# v7_h_no_callsign.net
KiCad netlist of a schematic drawn in EasyEDA Pro
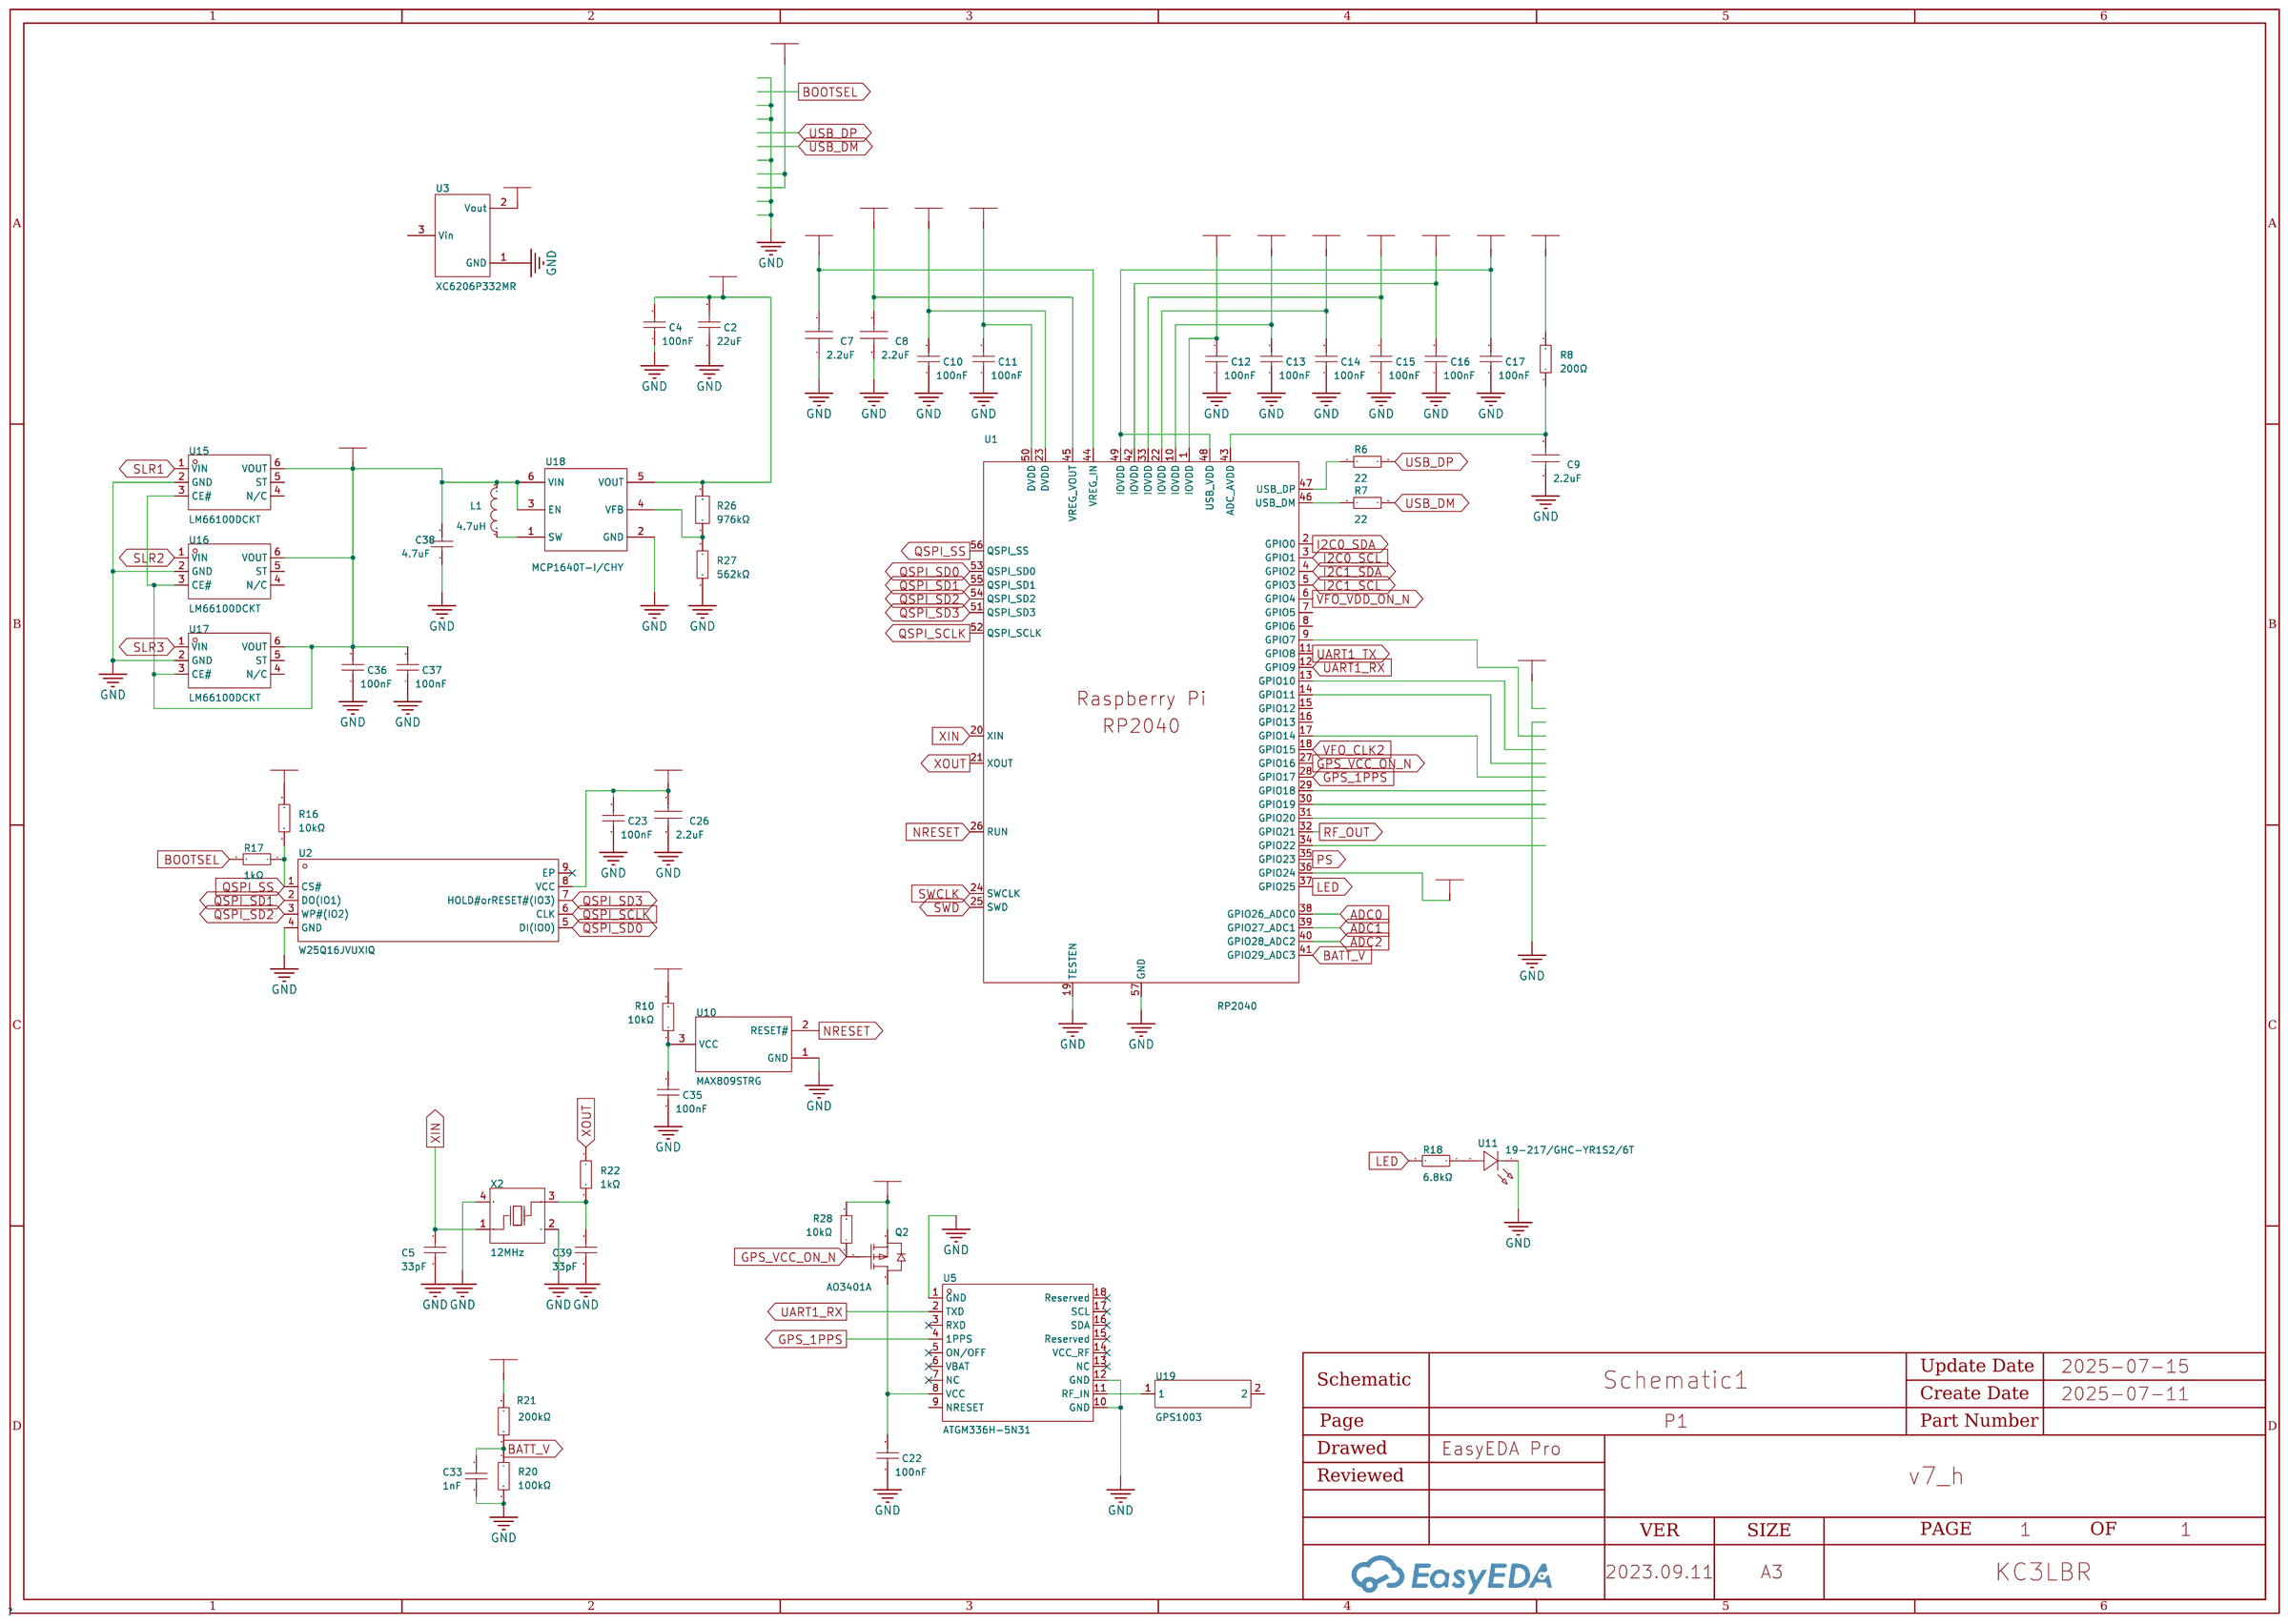
[diagram p0: schematic sheet]

(export (version "E")
  (design (tool "Eeschema 10.0.6"))
  (components
    (comp (ref "C2")
      (value "22uF")
      (footprint "easyedapro:C0603")
      (fields
        (field (name "Manufacturer Part") "CL10A226MQ8NRNC")
        (field (name "Manufacturer") "SAMSUNG(三星)")
      )
      (libsource (lib "easyedapro") (part "CL10A226MQ8NRNC"))
    )
    (comp (ref "C4")
      (value "100nF")
      (footprint "easyedapro:C0402_NEW")
      (fields
        (field (name "Manufacturer Part") "CL05B104KO5NNNC")
        (field (name "Manufacturer") "SAMSUNG(三星)")
      )
      (libsource (lib "easyedapro") (part "CL05B104KO5NNNC"))
    )
    (comp (ref "C5")
      (value "33pF")
      (footprint "easyedapro:C0402")
      (fields (field (name "Manufacturer Part") "0402CG330J500NT") (field (name "Manufacturer") "FH(风华)"))
      (libsource (lib "easyedapro") (part "0402CG330J500NT"))
    )
    (comp (ref "C7")
      (value "2.2uF")
      (footprint "easyedapro:C0402")
      (fields
        (field (name "Manufacturer Part") "CL05A225MQ5NSNC")
        (field (name "Manufacturer") "SAMSUNG(三星)")
      )
      (libsource (lib "easyedapro") (part "CL05A225MQ5NSNC"))
    )
    (comp (ref "C8")
      (value "2.2uF")
      (footprint "easyedapro:C0402")
      (fields
        (field (name "Manufacturer Part") "CL05A225MQ5NSNC")
        (field (name "Manufacturer") "SAMSUNG(三星)")
      )
      (libsource (lib "easyedapro") (part "CL05A225MQ5NSNC"))
    )
    (comp (ref "C9")
      (value "2.2uF")
      (footprint "easyedapro:C0402")
      (fields
        (field (name "Manufacturer Part") "CL05A225MQ5NSNC")
        (field (name "Manufacturer") "SAMSUNG(三星)")
      )
      (libsource (lib "easyedapro") (part "CL05A225MQ5NSNC"))
    )
    (comp (ref "C10")
      (value "100nF")
      (footprint "easyedapro:C0402_NEW")
      (fields
        (field (name "Manufacturer Part") "CL05B104KO5NNNC")
        (field (name "Manufacturer") "SAMSUNG(三星)")
      )
      (libsource (lib "easyedapro") (part "CL05B104KO5NNNC"))
    )
    (comp (ref "C11")
      (value "100nF")
      (footprint "easyedapro:C0402_NEW")
      (fields
        (field (name "Manufacturer Part") "CL05B104KO5NNNC")
        (field (name "Manufacturer") "SAMSUNG(三星)")
      )
      (libsource (lib "easyedapro") (part "CL05B104KO5NNNC"))
    )
    (comp (ref "C12")
      (value "100nF")
      (footprint "easyedapro:C0402_NEW")
      (fields
        (field (name "Manufacturer Part") "CL05B104KO5NNNC")
        (field (name "Manufacturer") "SAMSUNG(三星)")
      )
      (libsource (lib "easyedapro") (part "CL05B104KO5NNNC"))
    )
    (comp (ref "C13")
      (value "100nF")
      (footprint "easyedapro:C0402_NEW")
      (fields
        (field (name "Manufacturer Part") "CL05B104KO5NNNC")
        (field (name "Manufacturer") "SAMSUNG(三星)")
      )
      (libsource (lib "easyedapro") (part "CL05B104KO5NNNC"))
    )
    (comp (ref "C14")
      (value "100nF")
      (footprint "easyedapro:C0402_NEW")
      (fields
        (field (name "Manufacturer Part") "CL05B104KO5NNNC")
        (field (name "Manufacturer") "SAMSUNG(三星)")
      )
      (libsource (lib "easyedapro") (part "CL05B104KO5NNNC"))
    )
    (comp (ref "C15")
      (value "100nF")
      (footprint "easyedapro:C0402_NEW")
      (fields
        (field (name "Manufacturer Part") "CL05B104KO5NNNC")
        (field (name "Manufacturer") "SAMSUNG(三星)")
      )
      (libsource (lib "easyedapro") (part "CL05B104KO5NNNC"))
    )
    (comp (ref "C16")
      (value "100nF")
      (footprint "easyedapro:C0402_NEW")
      (fields
        (field (name "Manufacturer Part") "CL05B104KO5NNNC")
        (field (name "Manufacturer") "SAMSUNG(三星)")
      )
      (libsource (lib "easyedapro") (part "CL05B104KO5NNNC"))
    )
    (comp (ref "C17")
      (value "100nF")
      (footprint "easyedapro:C0402_NEW")
      (fields
        (field (name "Manufacturer Part") "CL05B104KO5NNNC")
        (field (name "Manufacturer") "SAMSUNG(三星)")
      )
      (libsource (lib "easyedapro") (part "CL05B104KO5NNNC"))
    )
    (comp (ref "C22")
      (value "100nF")
      (footprint "easyedapro:C0402_NEW")
      (fields
        (field (name "Manufacturer Part") "CL05B104KO5NNNC")
        (field (name "Manufacturer") "SAMSUNG(三星)")
      )
      (libsource (lib "easyedapro") (part "CL05B104KO5NNNC"))
    )
    (comp (ref "C23")
      (value "100nF")
      (footprint "easyedapro:C0402_NEW")
      (fields
        (field (name "Manufacturer Part") "CL05B104KO5NNNC")
        (field (name "Manufacturer") "SAMSUNG(三星)")
      )
      (libsource (lib "easyedapro") (part "CL05B104KO5NNNC"))
    )
    (comp (ref "C26")
      (value "2.2uF")
      (footprint "easyedapro:C0402")
      (fields
        (field (name "Manufacturer Part") "CL05A225MQ5NSNC")
        (field (name "Manufacturer") "SAMSUNG(三星)")
      )
      (libsource (lib "easyedapro") (part "CL05A225MQ5NSNC"))
    )
    (comp (ref "C33")
      (value "1nF")
      (footprint "easyedapro:C0402")
      (fields (field (name "Manufacturer Part") "0402B102K500NT") (field (name "Manufacturer") "FH(风华)"))
      (libsource (lib "easyedapro") (part "0402B102K500NT"))
    )
    (comp (ref "C35")
      (value "100nF")
      (footprint "easyedapro:C0402_NEW")
      (fields
        (field (name "Manufacturer Part") "CL05B104KO5NNNC")
        (field (name "Manufacturer") "SAMSUNG(三星)")
      )
      (libsource (lib "easyedapro") (part "CL05B104KO5NNNC"))
    )
    (comp (ref "C36")
      (value "100nF")
      (footprint "easyedapro:C0402_NEW")
      (fields
        (field (name "Manufacturer Part") "CL05B104KO5NNNC")
        (field (name "Manufacturer") "SAMSUNG(三星)")
      )
      (libsource (lib "easyedapro") (part "CL05B104KO5NNNC"))
    )
    (comp (ref "C37")
      (value "100nF")
      (footprint "easyedapro:C0402_NEW")
      (fields
        (field (name "Manufacturer Part") "CL05B104KO5NNNC")
        (field (name "Manufacturer") "SAMSUNG(三星)")
      )
      (libsource (lib "easyedapro") (part "CL05B104KO5NNNC"))
    )
    (comp (ref "C38")
      (value "4.7uF")
      (footprint "easyedapro:C0603")
      (fields
        (field (name "Manufacturer Part") "CL10A475KO8NNNC")
        (field (name "Manufacturer") "SAMSUNG(三星)")
      )
      (libsource (lib "easyedapro") (part "CL10A475KO8NNNC"))
    )
    (comp (ref "C39")
      (value "33pF")
      (footprint "easyedapro:C0402")
      (fields (field (name "Manufacturer Part") "0402CG330J500NT") (field (name "Manufacturer") "FH(风华)"))
      (libsource (lib "easyedapro") (part "0402CG330J500NT"))
    )
    (comp (ref "L1")
      (value "4.7uH")
      (footprint "easyedapro:IND-SMD_L2.5-W1.8")
      (fields
        (field (name "Manufacturer Part") "CBC2518T4R7M")
        (field (name "Manufacturer") "TAIYO YUDEN(太诱)")
      )
      (libsource (lib "easyedapro") (part "CBC2518T4R7M"))
    )
    (comp (ref "Q2")
      (value "AO3401A")
      (footprint "easyedapro:SOT-23_L2.9-W1.3-P1.90-LS2.4-BR")
      (fields (field (name "Manufacturer") "AOS"))
      (libsource (lib "easyedapro") (part "AO3401A"))
    )
    (comp (ref "R6")
      (value "22")
      (footprint "easyedapro:R0402")
      (fields
        (field (name "Manufacturer Part") "0402WGF220JTCE")
        (field (name "Manufacturer") "UNI-ROYAL(厚声)")
      )
      (libsource (lib "easyedapro") (part "0402WGF220JTCE"))
    )
    (comp (ref "R7")
      (value "22")
      (footprint "easyedapro:R0402")
      (fields
        (field (name "Manufacturer Part") "0402WGF220JTCE")
        (field (name "Manufacturer") "UNI-ROYAL(厚声)")
      )
      (libsource (lib "easyedapro") (part "0402WGF220JTCE"))
    )
    (comp (ref "R8")
      (value "200Ω")
      (footprint "easyedapro:R0402")
      (fields
        (field (name "Manufacturer Part") "0402WGF2000TCE")
        (field (name "Manufacturer") "UNI-ROYAL(厚声)")
      )
      (libsource (lib "easyedapro") (part "0402WGF2000TCE"))
    )
    (comp (ref "R10")
      (value "10kΩ")
      (footprint "easyedapro:R0402")
      (fields
        (field (name "Manufacturer Part") "0402WGF1002TCE")
        (field (name "Manufacturer") "UNI-ROYAL(厚声)")
      )
      (libsource (lib "easyedapro") (part "0402WGF1002TCE"))
    )
    (comp (ref "R16")
      (value "10kΩ")
      (footprint "easyedapro:R0402")
      (fields
        (field (name "Manufacturer Part") "0402WGF1002TCE")
        (field (name "Manufacturer") "UNI-ROYAL(厚声)")
      )
      (libsource (lib "easyedapro") (part "0402WGF1002TCE"))
    )
    (comp (ref "R17")
      (value "1kΩ")
      (footprint "easyedapro:R0402")
      (fields
        (field (name "Manufacturer Part") "0402WGF1001TCE")
        (field (name "Manufacturer") "UNI-ROYAL(厚声)")
      )
      (libsource (lib "easyedapro") (part "0402WGF1001TCE"))
    )
    (comp (ref "R18")
      (value "6.8kΩ")
      (footprint "easyedapro:R0402")
      (fields
        (field (name "Manufacturer Part") "0402WGF6801TCE")
        (field (name "Manufacturer") "UNI-ROYAL(厚声)")
      )
      (libsource (lib "easyedapro") (part "0402WGF6801TCE"))
    )
    (comp (ref "R20")
      (value "100kΩ")
      (footprint "easyedapro:R0402")
      (fields
        (field (name "Manufacturer Part") "0402WGF1003TCE")
        (field (name "Manufacturer") "UNI-ROYAL(厚声)")
      )
      (libsource (lib "easyedapro") (part "0402WGF1003TCE"))
    )
    (comp (ref "R21")
      (value "200kΩ")
      (footprint "easyedapro:R0402")
      (fields
        (field (name "Manufacturer Part") "0402WGF2003TCE")
        (field (name "Manufacturer") "UNI-ROYAL(厚声)")
      )
      (libsource (lib "easyedapro") (part "0402WGF2003TCE"))
    )
    (comp (ref "R22")
      (value "1kΩ")
      (footprint "easyedapro:R0402")
      (fields
        (field (name "Manufacturer Part") "0402WGF1001TCE")
        (field (name "Manufacturer") "UNI-ROYAL(厚声)")
      )
      (libsource (lib "easyedapro") (part "0402WGF1001TCE"))
    )
    (comp (ref "R26")
      (value "976kΩ")
      (footprint "easyedapro:R0402")
      (fields (field (name "Manufacturer Part") "RC0402FR-07976KL") (field (name "Manufacturer") "YAGEO(国巨)"))
      (libsource (lib "easyedapro") (part "RC0402FR-07976KL"))
    )
    (comp (ref "R27")
      (value "562kΩ")
      (footprint "easyedapro:R0402")
      (fields (field (name "Manufacturer Part") "RC0402FR-07562KL") (field (name "Manufacturer") "YAGEO(国巨)"))
      (libsource (lib "easyedapro") (part "RC0402FR-07562KL"))
    )
    (comp (ref "R28")
      (value "10kΩ")
      (footprint "easyedapro:R0402")
      (fields
        (field (name "Manufacturer Part") "0402WGF1002TCE")
        (field (name "Manufacturer") "UNI-ROYAL(厚声)")
      )
      (libsource (lib "easyedapro") (part "0402WGF1002TCE"))
    )
    (comp (ref "U1")
      (value "RP2040")
      (footprint "easyedapro:LQFN-56_L7.0-W7.0-P0.4-EP")
      (fields (field (name "Manufacturer") "Raspberry Pi(树莓派)"))
      (libsource (lib "easyedapro") (part "RP2040"))
    )
    (comp (ref "U2")
      (value "W25Q16JVUXIQ")
      (footprint "easyedapro:USON-8_L3.0-W2.0-P0.50-BL-EP")
      (fields (field (name "Manufacturer") "WINBOND(华邦)"))
      (libsource (lib "easyedapro") (part "W25Q16JVUXIQ"))
    )
    (comp (ref "U3")
      (value "XC6206P332MR")
      (footprint "easyedapro:SOT-23-3_L2.9-W1.6-P1.90-LS2.8-BR")
      (fields (field (name "Manufacturer") "GOODWORK(固得沃克)"))
      (libsource (lib "easyedapro") (part "XC6206P332MR"))
    )
    (comp (ref "U5")
      (value "ATGM336H-5N31")
      (footprint "easyedapro:GPSM-SMD_ATGM336H-TR")
      (fields (field (name "Manufacturer") "杭州中科微"))
      (libsource (lib "easyedapro") (part "ATGM336H-5N31"))
    )
    (comp (ref "U10")
      (value "MAX809STRG")
      (footprint "easyedapro:SOT-23-3_L2.9-W1.6-P1.90-LS2.8-BR")
      (fields (field (name "Manufacturer") "onsemi(安森美)"))
      (libsource (lib "easyedapro") (part "MAX809STRG"))
    )
    (comp (ref "U11")
      (value "19-217/GHC-YR1S2/6T")
      (footprint "easyedapro:LED0603-RD_GREEN")
      (fields (field (name "Manufacturer") "EVERLIGHT(亿光)"))
      (libsource (lib "easyedapro") (part "19-217/GHC-YR1S2/6T"))
    )
    (comp (ref "U15")
      (value "LM66100DCKT")
      (footprint "easyedapro:SC-70-6_L2.0-W1.3-P0.65-LS2.1-BL")
      (fields (field (name "Manufacturer") "TI(德州仪器)"))
      (libsource (lib "easyedapro") (part "LM66100DCKT"))
    )
    (comp (ref "U16")
      (value "LM66100DCKT")
      (footprint "easyedapro:SC-70-6_L2.0-W1.3-P0.65-LS2.1-BL")
      (fields (field (name "Manufacturer") "TI(德州仪器)"))
      (libsource (lib "easyedapro") (part "LM66100DCKT"))
    )
    (comp (ref "U17")
      (value "LM66100DCKT")
      (footprint "easyedapro:SC-70-6_L2.0-W1.3-P0.65-LS2.1-BL")
      (fields (field (name "Manufacturer") "TI(德州仪器)"))
      (libsource (lib "easyedapro") (part "LM66100DCKT"))
    )
    (comp (ref "U18")
      (value "MCP1640T-I/CHY")
      (footprint "easyedapro:SOT-23-6_L2.9-W1.6-P0.95-LS2.8-BR")
      (fields (field (name "Manufacturer") "MICROCHIP(美国微芯)"))
      (libsource (lib "easyedapro") (part "MCP1640T-I/CHY"))
    )
    (comp (ref "U19")
      (value "GPS1003")
      (footprint "easyedapro:ANT-SMD_L10.0-W3.0")
      (fields (field (name "Manufacturer") "Rainsun(霖昱微)"))
      (libsource (lib "easyedapro") (part "GPS1003"))
    )
    (comp (ref "X2")
      (value "12MHz")
      (footprint "easyedapro:OSC-SMD_4P-L3.2-W2.5-BL")
      (fields (field (name "Manufacturer Part") "X322512MSB4SI") (field (name "Manufacturer") "YXC(扬兴晶振)"))
      (libsource (lib "easyedapro") (part "X322512MSB4SI"))
    )
  )
  (nets
    (net (code "1") (name "1V1") (class "Default")
      (node (ref "C10") (pin "2") (pinfunction "2_2") (pintype "input"))
      (node (ref "C11") (pin "2") (pinfunction "2_2") (pintype "input"))
      (node (ref "C8") (pin "2") (pinfunction "2_2") (pintype "input"))
      (node (ref "U1") (pin "23") (pinfunction "DVDD_23") (pintype "bidirectional"))
      (node (ref "U1") (pin "45") (pinfunction "VREG_VOUT_45") (pintype "bidirectional"))
      (node (ref "U1") (pin "50") (pinfunction "DVDD_50") (pintype "bidirectional"))
    )
    (net (code "2") (name "3V3") (class "Default")
      (node (ref "C12") (pin "2") (pinfunction "2_2") (pintype "input"))
      (node (ref "C13") (pin "2") (pinfunction "2_2") (pintype "input"))
      (node (ref "C14") (pin "2") (pinfunction "2_2") (pintype "input"))
      (node (ref "C15") (pin "2") (pinfunction "2_2") (pintype "input"))
      (node (ref "C16") (pin "2") (pinfunction "2_2") (pintype "input"))
      (node (ref "C17") (pin "2") (pinfunction "2_2") (pintype "input"))
      (node (ref "C2") (pin "2") (pinfunction "2_2") (pintype "input"))
      (node (ref "C23") (pin "2") (pinfunction "2_2") (pintype "input"))
      (node (ref "C26") (pin "2") (pinfunction "2_2") (pintype "input"))
      (node (ref "C4") (pin "2") (pinfunction "2_2") (pintype "input"))
      (node (ref "C7") (pin "2") (pinfunction "2_2") (pintype "input"))
      (node (ref "Q2") (pin "2") (pinfunction "S_2") (pintype "input"))
      (node (ref "R10") (pin "2") (pinfunction "2_2") (pintype "input"))
      (node (ref "R16") (pin "2") (pinfunction "2_2") (pintype "input"))
      (node (ref "R26") (pin "2") (pinfunction "2_2") (pintype "unspecified"))
      (node (ref "R28") (pin "2") (pinfunction "2_2") (pintype "input"))
      (node (ref "R8") (pin "2") (pinfunction "2_2") (pintype "input"))
      (node (ref "U1") (pin "1") (pinfunction "IOVDD_1") (pintype "bidirectional"))
      (node (ref "U1") (pin "10") (pinfunction "IOVDD_10") (pintype "bidirectional"))
      (node (ref "U1") (pin "22") (pinfunction "IOVDD_22") (pintype "bidirectional"))
      (node (ref "U1") (pin "33") (pinfunction "IOVDD_33") (pintype "bidirectional"))
      (node (ref "U1") (pin "36") (pinfunction "GPIO24_36") (pintype "bidirectional"))
      (node (ref "U1") (pin "42") (pinfunction "IOVDD_42") (pintype "bidirectional"))
      (node (ref "U1") (pin "44") (pinfunction "VREG_IN_44") (pintype "bidirectional"))
      (node (ref "U1") (pin "48") (pinfunction "USB_VDD_48") (pintype "bidirectional"))
      (node (ref "U1") (pin "49") (pinfunction "IOVDD_49") (pintype "bidirectional"))
      (node (ref "U18") (pin "5") (pinfunction "VOUT_5") (pintype "input"))
      (node (ref "U2") (pin "8") (pinfunction "VCC_8") (pintype "input"))
      (node (ref "U3") (pin "2") (pinfunction "Vout_2") (pintype "input"))
    )
    (net (code "3") (name "ADC0") (class "Default")
      (node (ref "U1") (pin "38") (pinfunction "GPIO26_ADC0_38") (pintype "bidirectional"))
    )
    (net (code "4") (name "ADC1") (class "Default")
      (node (ref "U1") (pin "39") (pinfunction "GPIO27_ADC1_39") (pintype "bidirectional"))
    )
    (net (code "5") (name "ADC2") (class "Default")
      (node (ref "U1") (pin "40") (pinfunction "GPIO28_ADC2_40") (pintype "bidirectional"))
    )
    (net (code "6") (name "BATT_V") (class "Default")
      (node (ref "C33") (pin "2") (pinfunction "2_2") (pintype "input"))
      (node (ref "R20") (pin "1") (pinfunction "1_1") (pintype "input"))
      (node (ref "R21") (pin "1") (pinfunction "1_1") (pintype "input"))
      (node (ref "U1") (pin "41") (pinfunction "GPIO29_ADC3_41") (pintype "bidirectional"))
    )
    (net (code "7") (name "BOOTSEL") (class "Default")
      (node (ref "R17") (pin "2") (pinfunction "2_2") (pintype "input"))
    )
    (net (code "8") (name "GND") (class "Default")
      (node (ref "C10") (pin "1") (pinfunction "1_1") (pintype "input"))
      (node (ref "C11") (pin "1") (pinfunction "1_1") (pintype "input"))
      (node (ref "C12") (pin "1") (pinfunction "1_1") (pintype "input"))
      (node (ref "C13") (pin "1") (pinfunction "1_1") (pintype "input"))
      (node (ref "C14") (pin "1") (pinfunction "1_1") (pintype "input"))
      (node (ref "C15") (pin "1") (pinfunction "1_1") (pintype "input"))
      (node (ref "C16") (pin "1") (pinfunction "1_1") (pintype "input"))
      (node (ref "C17") (pin "1") (pinfunction "1_1") (pintype "input"))
      (node (ref "C2") (pin "1") (pinfunction "1_1") (pintype "input"))
      (node (ref "C22") (pin "1") (pinfunction "1_1") (pintype "input"))
      (node (ref "C23") (pin "1") (pinfunction "1_1") (pintype "input"))
      (node (ref "C26") (pin "1") (pinfunction "1_1") (pintype "input"))
      (node (ref "C33") (pin "1") (pinfunction "1_1") (pintype "input"))
      (node (ref "C35") (pin "1") (pinfunction "1_1") (pintype "input"))
      (node (ref "C36") (pin "1") (pinfunction "1_1") (pintype "input"))
      (node (ref "C37") (pin "1") (pinfunction "1_1") (pintype "input"))
      (node (ref "C38") (pin "1") (pinfunction "1_1") (pintype "input"))
      (node (ref "C39") (pin "1") (pinfunction "1_1") (pintype "input"))
      (node (ref "C4") (pin "1") (pinfunction "1_1") (pintype "input"))
      (node (ref "C5") (pin "1") (pinfunction "1_1") (pintype "input"))
      (node (ref "C7") (pin "1") (pinfunction "1_1") (pintype "input"))
      (node (ref "C8") (pin "1") (pinfunction "1_1") (pintype "input"))
      (node (ref "C9") (pin "1") (pinfunction "1_1") (pintype "input"))
      (node (ref "R20") (pin "2") (pinfunction "2_2") (pintype "input"))
      (node (ref "R27") (pin "1") (pinfunction "1_1") (pintype "unspecified"))
      (node (ref "U1") (pin "19") (pinfunction "TESTEN_19") (pintype "input"))
      (node (ref "U1") (pin "57") (pinfunction "GND_57") (pintype "bidirectional"))
      (node (ref "U10") (pin "1") (pinfunction "GND_1") (pintype "input"))
      (node (ref "U11") (pin "1") (pinfunction "K_1") (pintype "unspecified"))
      (node (ref "U15") (pin "2") (pinfunction "GND_2") (pintype "input"))
      (node (ref "U16") (pin "2") (pinfunction "GND_2") (pintype "input"))
      (node (ref "U17") (pin "2") (pinfunction "GND_2") (pintype "input"))
      (node (ref "U18") (pin "2") (pinfunction "GND_2") (pintype "input"))
      (node (ref "U2") (pin "4") (pinfunction "GND_4") (pintype "input"))
      (node (ref "U3") (pin "1") (pinfunction "GND_1") (pintype "input"))
      (node (ref "U5") (pin "1") (pinfunction "GND_1") (pintype "input"))
      (node (ref "U5") (pin "10") (pinfunction "GND_10") (pintype "input"))
      (node (ref "U5") (pin "12") (pinfunction "GND_12") (pintype "input"))
      (node (ref "X2") (pin "2") (pinfunction "GND_2") (pintype "input"))
      (node (ref "X2") (pin "4") (pinfunction "GND_4") (pintype "input"))
    )
    (net (code "9") (name "GPS_1PPS") (class "Default")
      (node (ref "U1") (pin "28") (pinfunction "GPIO17_28") (pintype "bidirectional"))
      (node (ref "U5") (pin "4") (pinfunction "1PPS_4") (pintype "input"))
    )
    (net (code "10") (name "GPS_VCC_ON_N") (class "Default")
      (node (ref "Q2") (pin "1") (pinfunction "G_1") (pintype "input"))
      (node (ref "R28") (pin "1") (pinfunction "1_1") (pintype "input"))
      (node (ref "U1") (pin "27") (pinfunction "GPIO16_27") (pintype "bidirectional"))
    )
    (net (code "11") (name "I2C0_SCL") (class "Default")
      (node (ref "U1") (pin "3") (pinfunction "GPIO1_3") (pintype "bidirectional"))
    )
    (net (code "12") (name "I2C0_SDA") (class "Default")
      (node (ref "U1") (pin "2") (pinfunction "GPIO0_2") (pintype "bidirectional"))
    )
    (net (code "13") (name "I2C1_SCL") (class "Default")
      (node (ref "U1") (pin "5") (pinfunction "GPIO3_5") (pintype "bidirectional"))
    )
    (net (code "14") (name "I2C1_SDA") (class "Default")
      (node (ref "U1") (pin "4") (pinfunction "GPIO2_4") (pintype "bidirectional"))
    )
    (net (code "15") (name "LED") (class "Default")
      (node (ref "R18") (pin "2") (pinfunction "2_2") (pintype "input"))
      (node (ref "U1") (pin "37") (pinfunction "GPIO25_37") (pintype "bidirectional"))
    )
    (net (code "16") (name "NRESET") (class "Default")
      (node (ref "U1") (pin "26") (pinfunction "RUN_26") (pintype "input"))
      (node (ref "U10") (pin "2") (pinfunction "RESET#_2") (pintype "input"))
    )
    (net (code "17") (name "Net-(Q2-D)") (class "Default")
      (node (ref "C22") (pin "2") (pinfunction "2_2") (pintype "input"))
      (node (ref "Q2") (pin "3") (pinfunction "D_3") (pintype "input"))
      (node (ref "U5") (pin "8") (pinfunction "VCC_8") (pintype "input"))
    )
    (net (code "18") (name "Net-(U1-ADC_AVDD)") (class "Default")
      (node (ref "C9") (pin "2") (pinfunction "2_2") (pintype "input"))
      (node (ref "R8") (pin "1") (pinfunction "1_1") (pintype "input"))
      (node (ref "U1") (pin "43") (pinfunction "ADC_AVDD_43") (pintype "bidirectional"))
    )
    (net (code "19") (name "Net-(U1-USB_DM)") (class "Default")
      (node (ref "R7") (pin "1") (pinfunction "1_1") (pintype "input"))
      (node (ref "U1") (pin "46") (pinfunction "USB_DM_46") (pintype "bidirectional"))
    )
    (net (code "20") (name "Net-(U1-USB_DP)") (class "Default")
      (node (ref "R6") (pin "1") (pinfunction "1_1") (pintype "input"))
      (node (ref "U1") (pin "47") (pinfunction "USB_DP_47") (pintype "bidirectional"))
    )
    (net (code "21") (name "Net-(U5-RF_IN)") (class "Default")
      (node (ref "U19") (pin "1") (pinfunction "1_1") (pintype "unspecified"))
      (node (ref "U5") (pin "11") (pinfunction "RF_IN_11") (pintype "input"))
    )
    (net (code "22") (name "Net-(U10-VCC)") (class "Default")
      (node (ref "C35") (pin "2") (pinfunction "2_2") (pintype "input"))
      (node (ref "R10") (pin "1") (pinfunction "1_1") (pintype "input"))
      (node (ref "U10") (pin "3") (pinfunction "VCC_3") (pintype "input"))
    )
    (net (code "23") (name "Net-(U11-A)") (class "Default")
      (node (ref "R18") (pin "1") (pinfunction "1_1") (pintype "input"))
      (node (ref "U11") (pin "2") (pinfunction "A_2") (pintype "unspecified"))
    )
    (net (code "24") (name "Net-(U18-SW)") (class "Default")
      (node (ref "L1") (pin "1") (pinfunction "1_1") (pintype "input"))
      (node (ref "U18") (pin "1") (pinfunction "SW_1") (pintype "input"))
    )
    (net (code "25") (name "Net-(U18-VFB)") (class "Default")
      (node (ref "R26") (pin "1") (pinfunction "1_1") (pintype "unspecified"))
      (node (ref "R27") (pin "2") (pinfunction "2_2") (pintype "unspecified"))
      (node (ref "U18") (pin "4") (pinfunction "VFB_4") (pintype "input"))
    )
    (net (code "26") (name "Net-(X2-OSC2)") (class "Default")
      (node (ref "C39") (pin "2") (pinfunction "2_2") (pintype "input"))
      (node (ref "R22") (pin "2") (pinfunction "2_2") (pintype "input"))
      (node (ref "X2") (pin "3") (pinfunction "OSC2_3") (pintype "input"))
    )
    (net (code "27") (name "PS") (class "Default")
      (node (ref "U1") (pin "35") (pinfunction "GPIO23_35") (pintype "bidirectional"))
    )
    (net (code "28") (name "QSPI_SCLK") (class "Default")
      (node (ref "U1") (pin "52") (pinfunction "QSPI_SCLK_52") (pintype "output"))
      (node (ref "U2") (pin "6") (pinfunction "CLK_6") (pintype "input"))
    )
    (net (code "29") (name "QSPI_SD0") (class "Default")
      (node (ref "U1") (pin "53") (pinfunction "QSPI_SD0_53") (pintype "bidirectional"))
      (node (ref "U2") (pin "5") (pinfunction "DI(IO0)_5") (pintype "input"))
    )
    (net (code "30") (name "QSPI_SD1") (class "Default")
      (node (ref "U1") (pin "55") (pinfunction "QSPI_SD1_55") (pintype "bidirectional"))
      (node (ref "U2") (pin "2") (pinfunction "DO(IO1)_2") (pintype "input"))
    )
    (net (code "31") (name "QSPI_SD2") (class "Default")
      (node (ref "U1") (pin "54") (pinfunction "QSPI_SD2_54") (pintype "bidirectional"))
      (node (ref "U2") (pin "3") (pinfunction "WP#(IO2)_3") (pintype "input"))
    )
    (net (code "32") (name "QSPI_SD3") (class "Default")
      (node (ref "U1") (pin "51") (pinfunction "QSPI_SD3_51") (pintype "bidirectional"))
      (node (ref "U2") (pin "7") (pinfunction "HOLD#orRESET#(IO3)_7") (pintype "input"))
    )
    (net (code "33") (name "QSPI_SS") (class "Default")
      (node (ref "R16") (pin "1") (pinfunction "1_1") (pintype "input"))
      (node (ref "R17") (pin "1") (pinfunction "1_1") (pintype "input"))
      (node (ref "U1") (pin "56") (pinfunction "QSPI_SS_56") (pintype "bidirectional"))
      (node (ref "U2") (pin "1") (pinfunction "CS#_1") (pintype "input"))
    )
    (net (code "34") (name "RF_OUT") (class "Default")
      (node (ref "U1") (pin "32") (pinfunction "GPIO21_32") (pintype "bidirectional"))
    )
    (net (code "35") (name "SLR1") (class "Default")
      (node (ref "U15") (pin "1") (pinfunction "VIN_1") (pintype "input"))
    )
    (net (code "36") (name "SLR2") (class "Default")
      (node (ref "U16") (pin "1") (pinfunction "VIN_1") (pintype "input"))
    )
    (net (code "37") (name "SLR3") (class "Default")
      (node (ref "U17") (pin "1") (pinfunction "VIN_1") (pintype "input"))
    )
    (net (code "38") (name "SWCLK") (class "Default")
      (node (ref "U1") (pin "24") (pinfunction "SWCLK_24") (pintype "output"))
    )
    (net (code "39") (name "SWD") (class "Default")
      (node (ref "U1") (pin "25") (pinfunction "SWD_25") (pintype "bidirectional"))
    )
    (net (code "40") (name "UART1_RX") (class "Default")
      (node (ref "U1") (pin "12") (pinfunction "GPIO9_12") (pintype "bidirectional"))
      (node (ref "U5") (pin "2") (pinfunction "TXD_2") (pintype "input"))
    )
    (net (code "41") (name "UART1_TX") (class "Default")
      (node (ref "U1") (pin "11") (pinfunction "GPIO8_11") (pintype "bidirectional"))
    )
    (net (code "42") (name "USB_DM") (class "Default")
      (node (ref "R7") (pin "2") (pinfunction "2_2") (pintype "input"))
    )
    (net (code "43") (name "USB_DP") (class "Default")
      (node (ref "R6") (pin "2") (pinfunction "2_2") (pintype "input"))
    )
    (net (code "44") (name "VBUS") (class "Default")
      (node (ref "C36") (pin "2") (pinfunction "2_2") (pintype "input"))
      (node (ref "C37") (pin "2") (pinfunction "2_2") (pintype "input"))
      (node (ref "C38") (pin "2") (pinfunction "2_2") (pintype "input"))
      (node (ref "L1") (pin "2") (pinfunction "2_2") (pintype "input"))
      (node (ref "R21") (pin "2") (pinfunction "2_2") (pintype "input"))
      (node (ref "U15") (pin "3") (pinfunction "CE#_3") (pintype "input"))
      (node (ref "U15") (pin "6") (pinfunction "VOUT_6") (pintype "input"))
      (node (ref "U16") (pin "3") (pinfunction "CE#_3") (pintype "input"))
      (node (ref "U16") (pin "6") (pinfunction "VOUT_6") (pintype "input"))
      (node (ref "U17") (pin "3") (pinfunction "CE#_3") (pintype "input"))
      (node (ref "U17") (pin "6") (pinfunction "VOUT_6") (pintype "input"))
      (node (ref "U18") (pin "3") (pinfunction "EN_3") (pintype "input"))
      (node (ref "U18") (pin "6") (pinfunction "VIN_6") (pintype "input"))
    )
    (net (code "45") (name "VFO_CLK2") (class "Default")
      (node (ref "U1") (pin "18") (pinfunction "GPIO15_18") (pintype "bidirectional"))
    )
    (net (code "46") (name "VFO_VDD_ON_N") (class "Default")
      (node (ref "U1") (pin "6") (pinfunction "GPIO4_6") (pintype "bidirectional"))
    )
    (net (code "47") (name "XIN") (class "Default")
      (node (ref "C5") (pin "2") (pinfunction "2_2") (pintype "input"))
      (node (ref "U1") (pin "20") (pinfunction "XIN_20") (pintype "input"))
      (node (ref "X2") (pin "1") (pinfunction "OSC1_1") (pintype "input"))
    )
    (net (code "48") (name "XOUT") (class "Default")
      (node (ref "R22") (pin "1") (pinfunction "1_1") (pintype "input"))
      (node (ref "U1") (pin "21") (pinfunction "XOUT_21") (pintype "input"))
    )
    (net (code "49") (name "unconnected-(U1-GPIO5-Pad7)") (class "Default")
      (node (ref "U1") (pin "7") (pinfunction "GPIO5_7") (pintype "bidirectional"))
    )
    (net (code "50") (name "unconnected-(U1-GPIO6-Pad8)") (class "Default")
      (node (ref "U1") (pin "8") (pinfunction "GPIO6_8") (pintype "bidirectional"))
    )
    (net (code "51") (name "unconnected-(U1-GPIO7-Pad9)") (class "Default")
      (node (ref "U1") (pin "9") (pinfunction "GPIO7_9") (pintype "bidirectional"))
    )
    (net (code "52") (name "unconnected-(U1-GPIO10-Pad13)") (class "Default")
      (node (ref "U1") (pin "13") (pinfunction "GPIO10_13") (pintype "bidirectional"))
    )
    (net (code "53") (name "unconnected-(U1-GPIO11-Pad14)") (class "Default")
      (node (ref "U1") (pin "14") (pinfunction "GPIO11_14") (pintype "bidirectional"))
    )
    (net (code "54") (name "unconnected-(U1-GPIO12-Pad15)") (class "Default")
      (node (ref "U1") (pin "15") (pinfunction "GPIO12_15") (pintype "bidirectional"))
    )
    (net (code "55") (name "unconnected-(U1-GPIO13-Pad16)") (class "Default")
      (node (ref "U1") (pin "16") (pinfunction "GPIO13_16") (pintype "bidirectional"))
    )
    (net (code "56") (name "unconnected-(U1-GPIO14-Pad17)") (class "Default")
      (node (ref "U1") (pin "17") (pinfunction "GPIO14_17") (pintype "bidirectional"))
    )
    (net (code "57") (name "unconnected-(U1-GPIO18-Pad29)") (class "Default")
      (node (ref "U1") (pin "29") (pinfunction "GPIO18_29") (pintype "bidirectional"))
    )
    (net (code "58") (name "unconnected-(U1-GPIO19-Pad30)") (class "Default")
      (node (ref "U1") (pin "30") (pinfunction "GPIO19_30") (pintype "bidirectional"))
    )
    (net (code "59") (name "unconnected-(U1-GPIO20-Pad31)") (class "Default")
      (node (ref "U1") (pin "31") (pinfunction "GPIO20_31") (pintype "bidirectional"))
    )
    (net (code "60") (name "unconnected-(U1-GPIO22-Pad34)") (class "Default")
      (node (ref "U1") (pin "34") (pinfunction "GPIO22_34") (pintype "bidirectional"))
    )
    (net (code "61") (name "unconnected-(U2-EP-Pad9)") (class "Default")
      (node (ref "U2") (pin "9") (pinfunction "EP_9") (pintype "input+no_connect"))
    )
    (net (code "62") (name "unconnected-(U3-Vin-Pad3)") (class "Default")
      (node (ref "U3") (pin "3") (pinfunction "Vin_3") (pintype "input"))
    )
    (net (code "63") (name "unconnected-(U5-NC-Pad7)") (class "Default")
      (node (ref "U5") (pin "7") (pinfunction "NC_7") (pintype "input+no_connect"))
    )
    (net (code "64") (name "unconnected-(U5-NC-Pad13)") (class "Default")
      (node (ref "U5") (pin "13") (pinfunction "NC_13") (pintype "input+no_connect"))
    )
    (net (code "65") (name "unconnected-(U5-NRESET-Pad9)") (class "Default")
      (node (ref "U5") (pin "9") (pinfunction "NRESET_9") (pintype "input"))
    )
    (net (code "66") (name "unconnected-(U5-ON{slash}OFF-Pad5)") (class "Default")
      (node (ref "U5") (pin "5") (pinfunction "ON/OFF_5") (pintype "input+no_connect"))
    )
    (net (code "67") (name "unconnected-(U5-RXD-Pad3)") (class "Default")
      (node (ref "U5") (pin "3") (pinfunction "RXD_3") (pintype "input+no_connect"))
    )
    (net (code "68") (name "unconnected-(U5-Reserved-Pad15)") (class "Default")
      (node (ref "U5") (pin "15") (pinfunction "Reserved_15") (pintype "input+no_connect"))
    )
    (net (code "69") (name "unconnected-(U5-Reserved-Pad18)") (class "Default")
      (node (ref "U5") (pin "18") (pinfunction "Reserved_18") (pintype "input+no_connect"))
    )
    (net (code "70") (name "unconnected-(U5-SCL-Pad17)") (class "Default")
      (node (ref "U5") (pin "17") (pinfunction "SCL_17") (pintype "input+no_connect"))
    )
    (net (code "71") (name "unconnected-(U5-SDA-Pad16)") (class "Default")
      (node (ref "U5") (pin "16") (pinfunction "SDA_16") (pintype "input+no_connect"))
    )
    (net (code "72") (name "unconnected-(U5-VBAT-Pad6)") (class "Default")
      (node (ref "U5") (pin "6") (pinfunction "VBAT_6") (pintype "input+no_connect"))
    )
    (net (code "73") (name "unconnected-(U5-VCC_RF-Pad14)") (class "Default")
      (node (ref "U5") (pin "14") (pinfunction "VCC_RF_14") (pintype "input+no_connect"))
    )
    (net (code "74") (name "unconnected-(U15-N{slash}C-Pad4)") (class "Default")
      (node (ref "U15") (pin "4") (pinfunction "N/C_4") (pintype "input"))
    )
    (net (code "75") (name "unconnected-(U15-ST-Pad5)") (class "Default")
      (node (ref "U15") (pin "5") (pinfunction "ST_5") (pintype "input"))
    )
    (net (code "76") (name "unconnected-(U16-N{slash}C-Pad4)") (class "Default")
      (node (ref "U16") (pin "4") (pinfunction "N/C_4") (pintype "input"))
    )
    (net (code "77") (name "unconnected-(U16-ST-Pad5)") (class "Default")
      (node (ref "U16") (pin "5") (pinfunction "ST_5") (pintype "input"))
    )
    (net (code "78") (name "unconnected-(U17-N{slash}C-Pad4)") (class "Default")
      (node (ref "U17") (pin "4") (pinfunction "N/C_4") (pintype "input"))
    )
    (net (code "79") (name "unconnected-(U17-ST-Pad5)") (class "Default")
      (node (ref "U17") (pin "5") (pinfunction "ST_5") (pintype "input"))
    )
    (net (code "80") (name "unconnected-(U19-Pad2)") (class "Default")
      (node (ref "U19") (pin "2") (pinfunction "2_2") (pintype "unspecified"))
    )
  )
)
